# 03_Mos.net
KiCad netlist of a schematic drawn in Altium Designer
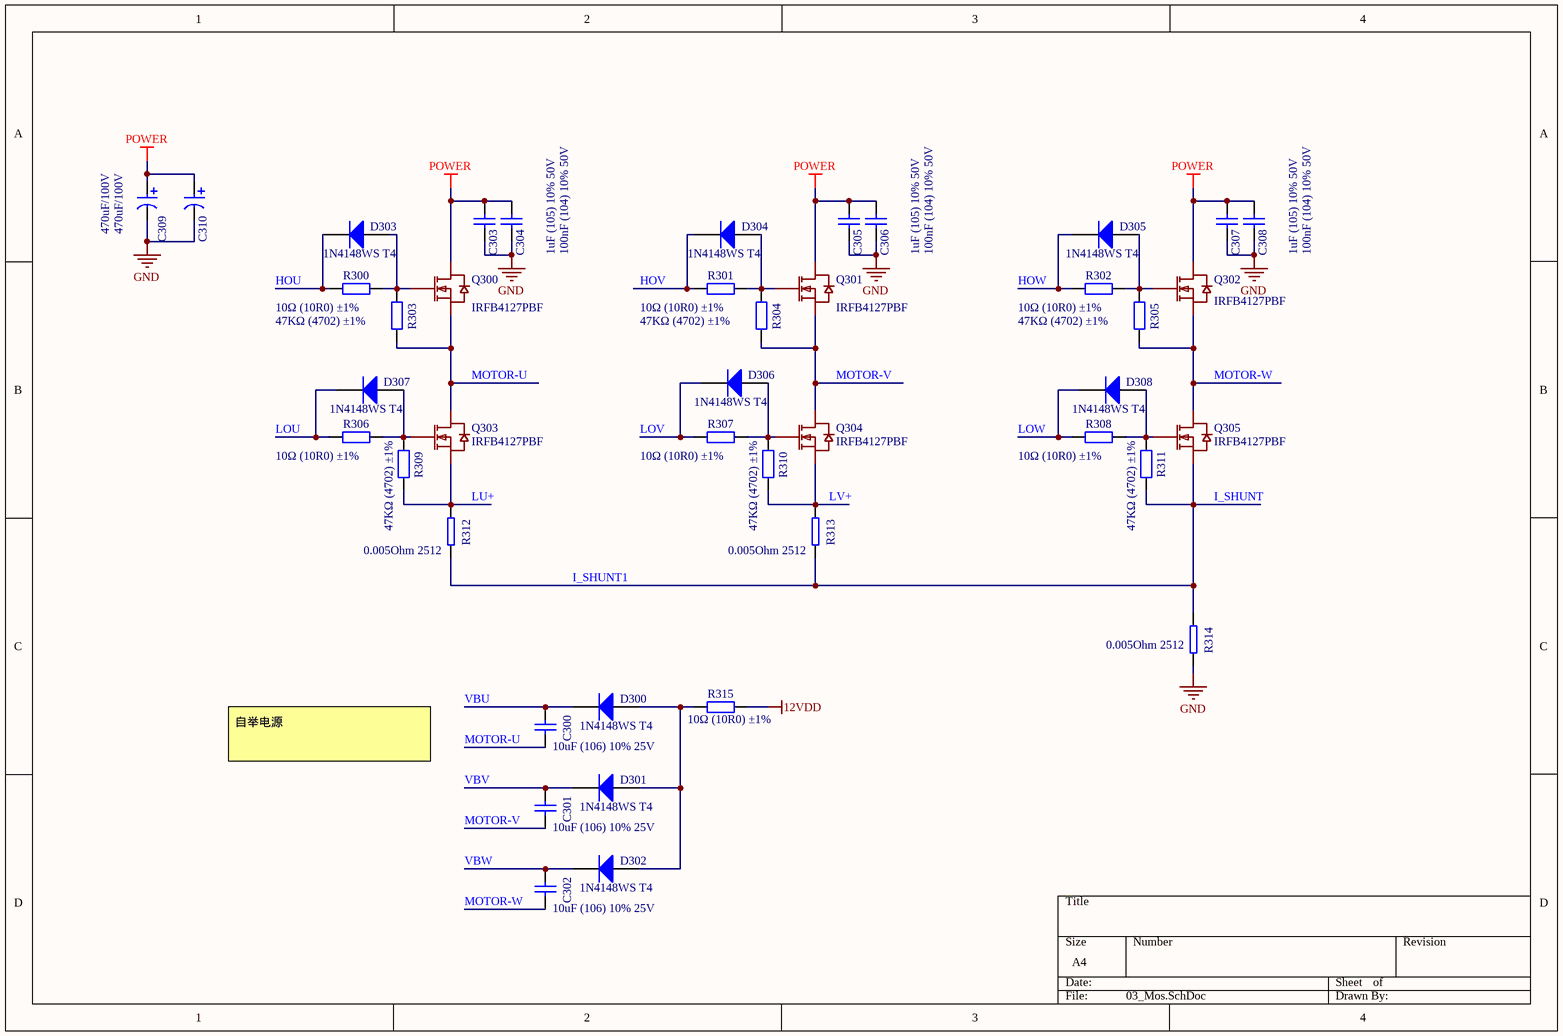
[diagram p0: 03_Mos.SchDoc]

(export (version "E")
  (design (tool "Eeschema 10.0.6"))
  (components
    (comp (ref "C300")
      (value "10uF (106) 10% 25V")
      (footprint "0805_C")
      (description "贴片电容")
      (libsource (lib "Miscellaneous Devices LC") (part "0805 10uF (106) 10% 25V"))
    )
    (comp (ref "C301")
      (value "10uF (106) 10% 25V")
      (footprint "0805_C")
      (description "贴片电容")
      (libsource (lib "Miscellaneous Devices LC") (part "0805 10uF (106) 10% 25V"))
    )
    (comp (ref "C302")
      (value "10uF (106) 10% 25V")
      (footprint "0805_C")
      (description "贴片电容")
      (libsource (lib "Miscellaneous Devices LC") (part "0805 10uF (106) 10% 25V"))
    )
    (comp (ref "C303")
      (value "100nF (104) 10% 50V")
      (footprint "1206_C")
      (description "贴片电容")
      (libsource (lib "Miscellaneous Devices LC") (part "1206 100nF (104) 10% 50V"))
    )
    (comp (ref "C304")
      (value "1uF (105) 10% 50V")
      (footprint "1206_C")
      (description "贴片电容")
      (libsource (lib "Miscellaneous Devices LC") (part "1206 1uF (105) 10% 50V"))
    )
    (comp (ref "C305")
      (value "100nF (104) 10% 50V")
      (footprint "1206_C")
      (description "贴片电容")
      (libsource (lib "Miscellaneous Devices LC") (part "1206 100nF (104) 10% 50V"))
    )
    (comp (ref "C306")
      (value "1uF (105) 10% 50V")
      (footprint "1206_C")
      (description "贴片电容")
      (libsource (lib "Miscellaneous Devices LC") (part "1206 1uF (105) 10% 50V"))
    )
    (comp (ref "C307")
      (value "100nF (104) 10% 50V")
      (footprint "1206_C")
      (description "贴片电容")
      (libsource (lib "Miscellaneous Devices LC") (part "1206 100nF (104) 10% 50V"))
    )
    (comp (ref "C308")
      (value "1uF (105) 10% 50V")
      (footprint "1206_C")
      (description "贴片电容")
      (libsource (lib "Miscellaneous Devices LC") (part "1206 1uF (105) 10% 50V"))
    )
    (comp (ref "C309")
      (value "470uF/100V")
      (footprint "CAP_D16_L31.5")
      (description "电解电容")
      (libsource (lib "Schlibv2") (part "CAP2"))
    )
    (comp (ref "C310")
      (value "470uF/100V")
      (footprint "CAP_D16_L31.5")
      (description "电解电容")
      (libsource (lib "Schlibv2") (part "CAP2"))
    )
    (comp (ref "D300")
      (value "1N4148WS T4")
      (footprint "SOD-323")
      (description "二极管")
      (libsource (lib "Miscellaneous Devices LC") (part "SOD-323 1N4148WS T4"))
    )
    (comp (ref "D301")
      (value "1N4148WS T4")
      (footprint "SOD-323")
      (description "二极管")
      (libsource (lib "Miscellaneous Devices LC") (part "SOD-323 1N4148WS T4"))
    )
    (comp (ref "D302")
      (value "1N4148WS T4")
      (footprint "SOD-323")
      (description "二极管")
      (libsource (lib "Miscellaneous Devices LC") (part "SOD-323 1N4148WS T4"))
    )
    (comp (ref "D303")
      (value "1N4148WS T4")
      (footprint "SOD-323")
      (description "二极管")
      (libsource (lib "Miscellaneous Devices LC") (part "SOD-323 1N4148WS T4"))
    )
    (comp (ref "D304")
      (value "1N4148WS T4")
      (footprint "SOD-323")
      (description "二极管")
      (libsource (lib "Miscellaneous Devices LC") (part "SOD-323 1N4148WS T4"))
    )
    (comp (ref "D305")
      (value "1N4148WS T4")
      (footprint "SOD-323")
      (description "二极管")
      (libsource (lib "Miscellaneous Devices LC") (part "SOD-323 1N4148WS T4"))
    )
    (comp (ref "D306")
      (value "1N4148WS T4")
      (footprint "SOD-323")
      (description "二极管")
      (libsource (lib "Miscellaneous Devices LC") (part "SOD-323 1N4148WS T4"))
    )
    (comp (ref "D307")
      (value "1N4148WS T4")
      (footprint "SOD-323")
      (description "二极管")
      (libsource (lib "Miscellaneous Devices LC") (part "SOD-323 1N4148WS T4"))
    )
    (comp (ref "D308")
      (value "1N4148WS T4")
      (footprint "SOD-323")
      (description "二极管")
      (libsource (lib "Miscellaneous Devices LC") (part "SOD-323 1N4148WS T4"))
    )
    (comp (ref "Q300")
      (value "IRFB4127PBF")
      (footprint "IRFB4127")
      (libsource (lib "RayPCB20210502") (part "IRFB4127PBF"))
    )
    (comp (ref "Q301")
      (value "IRFB4127PBF")
      (footprint "IRFB4127")
      (libsource (lib "RayPCB20210502") (part "IRFB4127PBF"))
    )
    (comp (ref "Q302")
      (value "IRFB4127PBF")
      (footprint "IRFB4127")
      (libsource (lib "RayPCB20210502") (part "IRFB4127PBF"))
    )
    (comp (ref "Q303")
      (value "IRFB4127PBF")
      (footprint "IRFB4127")
      (libsource (lib "RayPCB20210502") (part "IRFB4127PBF"))
    )
    (comp (ref "Q304")
      (value "IRFB4127PBF")
      (footprint "IRFB4127")
      (libsource (lib "RayPCB20210502") (part "IRFB4127PBF"))
    )
    (comp (ref "Q305")
      (value "IRFB4127PBF")
      (footprint "IRFB4127")
      (libsource (lib "RayPCB20210502") (part "IRFB4127PBF"))
    )
    (comp (ref "R300")
      (value "10Ω (10R0) ±1%")
      (footprint "0805_R")
      (description "贴片电阻")
      (libsource (lib "Miscellaneous Devices LC") (part "0805 10Ω (10R0) 1%"))
    )
    (comp (ref "R301")
      (value "10Ω (10R0) ±1%")
      (footprint "0805_R")
      (description "贴片电阻")
      (libsource (lib "Miscellaneous Devices LC") (part "0805 10Ω (10R0) 1%"))
    )
    (comp (ref "R302")
      (value "10Ω (10R0) ±1%")
      (footprint "0805_R")
      (description "贴片电阻")
      (libsource (lib "Miscellaneous Devices LC") (part "0805 10Ω (10R0) 1%"))
    )
    (comp (ref "R303")
      (value "47KΩ (4702) ±1%")
      (footprint "0805_R")
      (description "贴片电阻")
      (libsource (lib "Miscellaneous Devices LC") (part "0805 47KΩ (4702) 1%"))
    )
    (comp (ref "R304")
      (value "47KΩ (4702) ±1%")
      (footprint "0805_R")
      (description "贴片电阻")
      (libsource (lib "Miscellaneous Devices LC") (part "0805 47KΩ (4702) 1%"))
    )
    (comp (ref "R305")
      (value "47KΩ (4702) ±1%")
      (footprint "0805_R")
      (description "贴片电阻")
      (libsource (lib "Miscellaneous Devices LC") (part "0805 47KΩ (4702) 1%"))
    )
    (comp (ref "R306")
      (value "10Ω (10R0) ±1%")
      (footprint "0805_R")
      (description "贴片电阻")
      (libsource (lib "Miscellaneous Devices LC") (part "0805 10Ω (10R0) 1%"))
    )
    (comp (ref "R307")
      (value "10Ω (10R0) ±1%")
      (footprint "0805_R")
      (description "贴片电阻")
      (libsource (lib "Miscellaneous Devices LC") (part "0805 10Ω (10R0) 1%"))
    )
    (comp (ref "R308")
      (value "10Ω (10R0) ±1%")
      (footprint "0805_R")
      (description "贴片电阻")
      (libsource (lib "Miscellaneous Devices LC") (part "0805 10Ω (10R0) 1%"))
    )
    (comp (ref "R309")
      (value "47KΩ (4702) ±1%")
      (footprint "0805_R")
      (description "贴片电阻")
      (libsource (lib "Miscellaneous Devices LC") (part "0805 47KΩ (4702) 1%"))
    )
    (comp (ref "R310")
      (value "47KΩ (4702) ±1%")
      (footprint "0805_R")
      (description "贴片电阻")
      (libsource (lib "Miscellaneous Devices LC") (part "0805 47KΩ (4702) 1%"))
    )
    (comp (ref "R311")
      (value "47KΩ (4702) ±1%")
      (footprint "0805_R")
      (description "贴片电阻")
      (libsource (lib "Miscellaneous Devices LC") (part "0805 47KΩ (4702) 1%"))
    )
    (comp (ref "R312")
      (value "0.005Ohm 2512")
      (footprint "R2512")
      (libsource (lib "RayPCB20210502") (part "Res10K"))
    )
    (comp (ref "R313")
      (value "0.005Ohm 2512")
      (footprint "R2512")
      (libsource (lib "RayPCB20210502") (part "Res10K"))
    )
    (comp (ref "R314")
      (value "0.005Ohm 2512")
      (footprint "R2512")
      (libsource (lib "RayPCB20210502") (part "Res10K"))
    )
    (comp (ref "R315")
      (value "10Ω (10R0) ±1%")
      (footprint "0805_R")
      (description "贴片电阻")
      (libsource (lib "Miscellaneous Devices LC") (part "0805 10Ω (10R0) 1%"))
    )
  )
  (nets
    (net (code "1") (name "/HOU") (class "Default")
      (node (ref "D303") (pin "2") (pinfunction "K_2") (pintype "passive"))
      (node (ref "R300") (pin "1") (pinfunction "1_1") (pintype "passive"))
    )
    (net (code "2") (name "/HOV") (class "Default")
      (node (ref "D304") (pin "2") (pinfunction "K_2") (pintype "passive"))
      (node (ref "R301") (pin "1") (pinfunction "1_1") (pintype "passive"))
    )
    (net (code "3") (name "/HOW") (class "Default")
      (node (ref "D305") (pin "2") (pinfunction "K_2") (pintype "passive"))
      (node (ref "R302") (pin "1") (pinfunction "1_1") (pintype "passive"))
    )
    (net (code "4") (name "/I_SHUNT") (class "Default")
      (node (ref "Q305") (pin "3") (pinfunction "S_3") (pintype "passive"))
      (node (ref "R311") (pin "1") (pinfunction "1_1") (pintype "passive"))
      (node (ref "R312") (pin "1") (pintype "passive"))
      (node (ref "R313") (pin "1") (pintype "passive"))
      (node (ref "R314") (pin "2") (pintype "passive"))
    )
    (net (code "5") (name "/LOU") (class "Default")
      (node (ref "D307") (pin "2") (pinfunction "K_2") (pintype "passive"))
      (node (ref "R306") (pin "1") (pinfunction "1_1") (pintype "passive"))
    )
    (net (code "6") (name "/LOV") (class "Default")
      (node (ref "D306") (pin "2") (pinfunction "K_2") (pintype "passive"))
      (node (ref "R307") (pin "1") (pinfunction "1_1") (pintype "passive"))
    )
    (net (code "7") (name "/LOW") (class "Default")
      (node (ref "D308") (pin "2") (pinfunction "K_2") (pintype "passive"))
      (node (ref "R308") (pin "1") (pinfunction "1_1") (pintype "passive"))
    )
    (net (code "8") (name "/LU+") (class "Default")
      (node (ref "Q303") (pin "3") (pinfunction "S_3") (pintype "passive"))
      (node (ref "R309") (pin "1") (pinfunction "1_1") (pintype "passive"))
      (node (ref "R312") (pin "2") (pintype "passive"))
    )
    (net (code "9") (name "/LV+") (class "Default")
      (node (ref "Q304") (pin "3") (pinfunction "S_3") (pintype "passive"))
      (node (ref "R310") (pin "1") (pinfunction "1_1") (pintype "passive"))
      (node (ref "R313") (pin "2") (pintype "passive"))
    )
    (net (code "10") (name "/MOTOR-U") (class "Default")
      (node (ref "C300") (pin "1") (pinfunction "1_1") (pintype "passive"))
      (node (ref "Q300") (pin "3") (pinfunction "S_3") (pintype "passive"))
      (node (ref "Q303") (pin "2") (pinfunction "D_2") (pintype "passive"))
      (node (ref "R303") (pin "1") (pinfunction "1_1") (pintype "passive"))
    )
    (net (code "11") (name "/MOTOR-V") (class "Default")
      (node (ref "C301") (pin "1") (pinfunction "1_1") (pintype "passive"))
      (node (ref "Q301") (pin "3") (pinfunction "S_3") (pintype "passive"))
      (node (ref "Q304") (pin "2") (pinfunction "D_2") (pintype "passive"))
      (node (ref "R304") (pin "1") (pinfunction "1_1") (pintype "passive"))
    )
    (net (code "12") (name "/MOTOR-W") (class "Default")
      (node (ref "C302") (pin "1") (pinfunction "1_1") (pintype "passive"))
      (node (ref "Q302") (pin "3") (pinfunction "S_3") (pintype "passive"))
      (node (ref "Q305") (pin "2") (pinfunction "D_2") (pintype "passive"))
      (node (ref "R305") (pin "1") (pinfunction "1_1") (pintype "passive"))
    )
    (net (code "13") (name "/VBU") (class "Default")
      (node (ref "C300") (pin "2") (pinfunction "2_2") (pintype "passive"))
      (node (ref "D300") (pin "2") (pinfunction "K_2") (pintype "passive"))
    )
    (net (code "14") (name "/VBV") (class "Default")
      (node (ref "C301") (pin "2") (pinfunction "2_2") (pintype "passive"))
      (node (ref "D301") (pin "2") (pinfunction "K_2") (pintype "passive"))
    )
    (net (code "15") (name "/VBW") (class "Default")
      (node (ref "C302") (pin "2") (pinfunction "2_2") (pintype "passive"))
      (node (ref "D302") (pin "2") (pinfunction "K_2") (pintype "passive"))
    )
    (net (code "16") (name "12VDD") (class "Default")
      (node (ref "R315") (pin "2") (pinfunction "2_2") (pintype "passive"))
    )
    (net (code "17") (name "GND") (class "Default")
      (node (ref "C303") (pin "1") (pinfunction "1_1") (pintype "passive"))
      (node (ref "C304") (pin "1") (pinfunction "1_1") (pintype "passive"))
      (node (ref "C305") (pin "1") (pinfunction "1_1") (pintype "passive"))
      (node (ref "C306") (pin "1") (pinfunction "1_1") (pintype "passive"))
      (node (ref "C307") (pin "1") (pinfunction "1_1") (pintype "passive"))
      (node (ref "C308") (pin "1") (pinfunction "1_1") (pintype "passive"))
      (node (ref "C309") (pin "2") (pintype "passive"))
      (node (ref "C310") (pin "2") (pintype "passive"))
      (node (ref "R314") (pin "1") (pintype "passive"))
    )
    (net (code "18") (name "Net-(D300-A)") (class "Default")
      (node (ref "D300") (pin "1") (pinfunction "A_1") (pintype "passive"))
      (node (ref "D301") (pin "1") (pinfunction "A_1") (pintype "passive"))
      (node (ref "D302") (pin "1") (pinfunction "A_1") (pintype "passive"))
      (node (ref "R315") (pin "1") (pinfunction "1_1") (pintype "passive"))
    )
    (net (code "19") (name "Net-(D303-A)") (class "Default")
      (node (ref "D303") (pin "1") (pinfunction "A_1") (pintype "passive"))
      (node (ref "Q300") (pin "1") (pinfunction "G_1") (pintype "passive"))
      (node (ref "R300") (pin "2") (pinfunction "2_2") (pintype "passive"))
      (node (ref "R303") (pin "2") (pinfunction "2_2") (pintype "passive"))
    )
    (net (code "20") (name "Net-(D304-A)") (class "Default")
      (node (ref "D304") (pin "1") (pinfunction "A_1") (pintype "passive"))
      (node (ref "Q301") (pin "1") (pinfunction "G_1") (pintype "passive"))
      (node (ref "R301") (pin "2") (pinfunction "2_2") (pintype "passive"))
      (node (ref "R304") (pin "2") (pinfunction "2_2") (pintype "passive"))
    )
    (net (code "21") (name "Net-(D305-A)") (class "Default")
      (node (ref "D305") (pin "1") (pinfunction "A_1") (pintype "passive"))
      (node (ref "Q302") (pin "1") (pinfunction "G_1") (pintype "passive"))
      (node (ref "R302") (pin "2") (pinfunction "2_2") (pintype "passive"))
      (node (ref "R305") (pin "2") (pinfunction "2_2") (pintype "passive"))
    )
    (net (code "22") (name "Net-(D306-A)") (class "Default")
      (node (ref "D306") (pin "1") (pinfunction "A_1") (pintype "passive"))
      (node (ref "Q304") (pin "1") (pinfunction "G_1") (pintype "passive"))
      (node (ref "R307") (pin "2") (pinfunction "2_2") (pintype "passive"))
      (node (ref "R310") (pin "2") (pinfunction "2_2") (pintype "passive"))
    )
    (net (code "23") (name "Net-(D307-A)") (class "Default")
      (node (ref "D307") (pin "1") (pinfunction "A_1") (pintype "passive"))
      (node (ref "Q303") (pin "1") (pinfunction "G_1") (pintype "passive"))
      (node (ref "R306") (pin "2") (pinfunction "2_2") (pintype "passive"))
      (node (ref "R309") (pin "2") (pinfunction "2_2") (pintype "passive"))
    )
    (net (code "24") (name "Net-(D308-A)") (class "Default")
      (node (ref "D308") (pin "1") (pinfunction "A_1") (pintype "passive"))
      (node (ref "Q305") (pin "1") (pinfunction "G_1") (pintype "passive"))
      (node (ref "R308") (pin "2") (pinfunction "2_2") (pintype "passive"))
      (node (ref "R311") (pin "2") (pinfunction "2_2") (pintype "passive"))
    )
    (net (code "25") (name "POWER") (class "Default")
      (node (ref "C303") (pin "2") (pinfunction "2_2") (pintype "passive"))
      (node (ref "C304") (pin "2") (pinfunction "2_2") (pintype "passive"))
      (node (ref "C305") (pin "2") (pinfunction "2_2") (pintype "passive"))
      (node (ref "C306") (pin "2") (pinfunction "2_2") (pintype "passive"))
      (node (ref "C307") (pin "2") (pinfunction "2_2") (pintype "passive"))
      (node (ref "C308") (pin "2") (pinfunction "2_2") (pintype "passive"))
      (node (ref "C309") (pin "1") (pintype "passive"))
      (node (ref "C310") (pin "1") (pintype "passive"))
      (node (ref "Q300") (pin "2") (pinfunction "D_2") (pintype "passive"))
      (node (ref "Q301") (pin "2") (pinfunction "D_2") (pintype "passive"))
      (node (ref "Q302") (pin "2") (pinfunction "D_2") (pintype "passive"))
    )
  )
)
